# Output_Display.net
KiCad netlist of a schematic drawn in Altium Designer
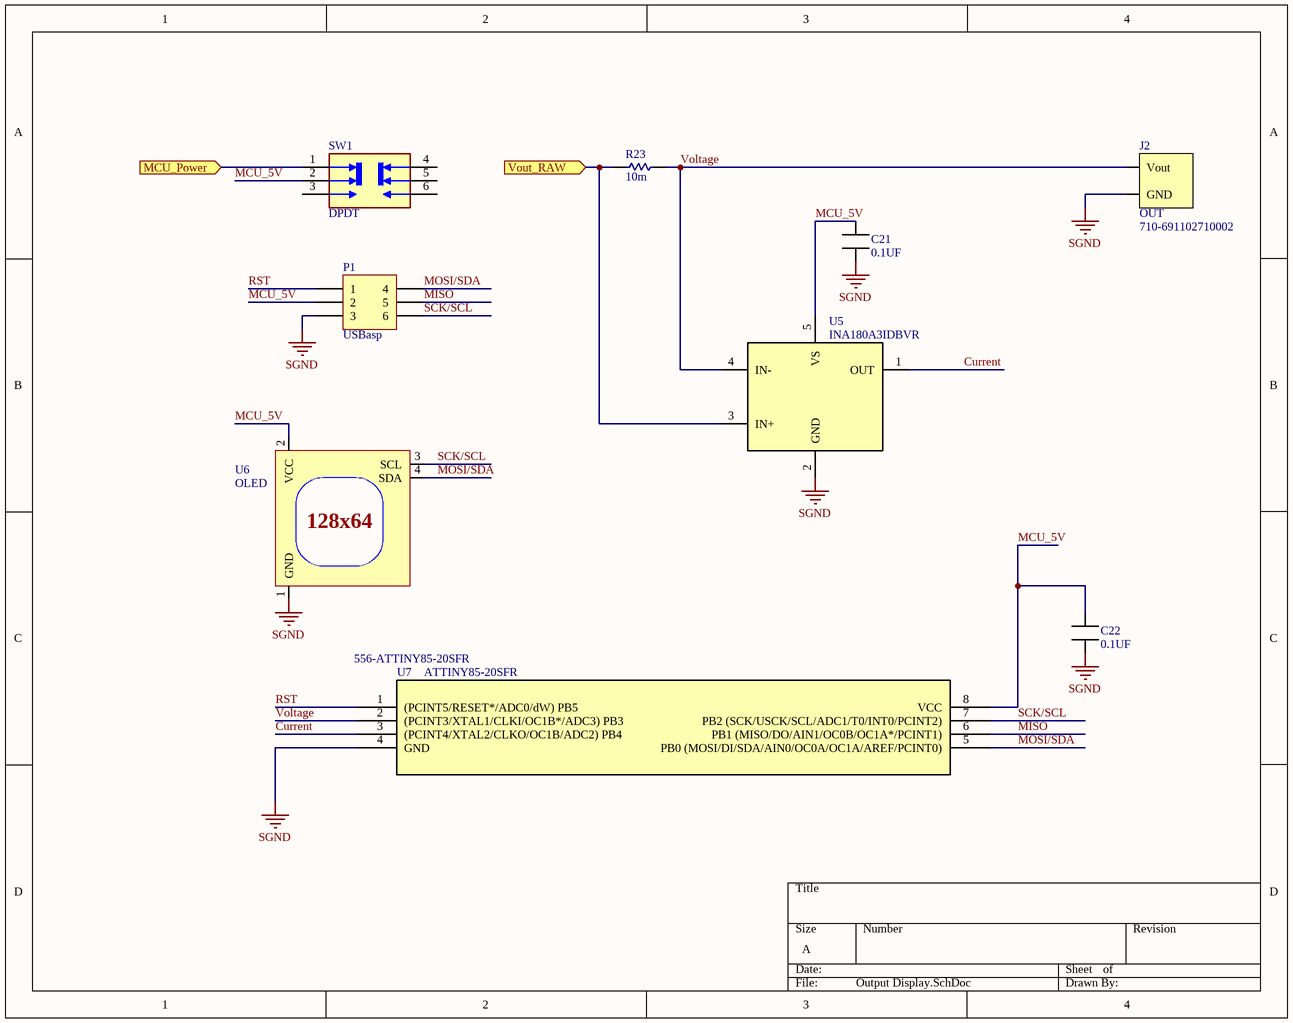
[diagram p0: Output Display.SchDoc]

(export (version "E")
  (design (tool "Eeschema 10.0.6"))
  (components
    (comp (ref "C21")
      (value "0.1UF")
      (footprint "Cap 0603")
      (description "Multilayer Ceramic Capacitors MLCC - SMD/SMT 25V 0.1uF X7R 0603 10%")
      (libsource (lib "SMPS Schlib") (part "C0603C104K3RAC"))
    )
    (comp (ref "C22")
      (value "0.1UF")
      (footprint "Cap 0603")
      (description "Multilayer Ceramic Capacitors MLCC - SMD/SMT 25V 0.1uF X7R 0603 10%")
      (libsource (lib "SMPS Schlib") (part "C0603C104K3RAC"))
    )
    (comp (ref "J2")
      (value "OUT")
      (footprint "691102710002")
      (description "Fixed Terminal Blocks WR-TBL 300VAC 15A 2P Straight")
      (fields (field (name "SUPPLIER PART NUMBER 1") "710-691102710002"))
      (libsource (lib "SMPS Schlib") (part "691102710002"))
    )
    (comp (ref "P1")
      (value "USBasp")
      (footprint "HDR2X3_CEN")
      (description "Header, 3-Pin, Dual row")
      (fields (field (name "PUBLISHER") "Altium Limited"))
      (libsource (lib "Miscellaneous Connectors") (part "Header 3X2A"))
    )
    (comp (ref "R23")
      (value "10m")
      (footprint "Cap 1206")
      (description "Current Sense Resistors - SMD 10mOhms 1/4W 50PPM/C 1 % 1206 AEC-Q200")
      (libsource (lib "SMPS Schlib") (part "PA1206FRE070R01Z"))
    )
    (comp (ref "SW1")
      (value "DPDT")
      (footprint "JS2020")
      (description "SWITCH SLIDE DPDT 300MA 6V")
      (libsource (lib "SMPS Schlib") (part "JS202011SCQN"))
    )
    (comp (ref "U5")
      (value "INA180A3IDBVR")
      (footprint "SOT-23-5")
      (description "Current Sense Amplifiers 26V, 350kHz current sense amplifier 5-SOT-23 -40 to 125")
      (libsource (lib "SMPS Schlib") (part "INA180A3IDBVR"))
    )
    (comp (ref "U6")
      (value "OLED")
      (footprint "OLED")
      (description "0.96″ OLED 4pin LCD LED Display Module I2C IIC Communicate – White 128×64")
      (libsource (lib "SMPS Schlib") (part "0.96 inch OLED"))
    )
    (comp (ref "U7")
      (value "ATTINY85-20SFR")
      (footprint "SOIC 8 ATTINY")
      (description "8-bit Microcontrollers - MCU AVR 8K FLSH 512B EE 512B SRAM ADC 5V")
      (fields (field (name "SUPPLIER PART NUMBER 1") "556-ATTINY85-20SFR"))
      (libsource (lib "SMPS Schlib") (part "ATTINY85-20SU"))
    )
  )
  (nets
    (net (code "1") (name "/Current") (class "Default")
      (node (ref "U5") (pin "1") (pinfunction "OUT_1") (pintype "passive"))
      (node (ref "U7") (pin "3") (pinfunction "(PCINT4/XTAL2/CLKO/OC1B/ADC2)_PB4_3") (pintype "passive"))
    )
    (net (code "2") (name "/MCU_5V") (class "Default")
      (node (ref "C21") (pin "2") (pinfunction "2_2") (pintype "passive"))
      (node (ref "C22") (pin "2") (pinfunction "2_2") (pintype "passive"))
      (node (ref "P1") (pin "2") (pinfunction "2_2") (pintype "passive"))
      (node (ref "SW1") (pin "2") (pinfunction "2_2") (pintype "passive"))
      (node (ref "U5") (pin "5") (pinfunction "VS_5") (pintype "power_in"))
      (node (ref "U6") (pin "2") (pinfunction "VCC_2") (pintype "passive"))
      (node (ref "U7") (pin "8") (pinfunction "VCC_8") (pintype "passive"))
    )
    (net (code "3") (name "/MCU_Power") (class "Default")
      (node (ref "SW1") (pin "1") (pinfunction "1_1") (pintype "passive"))
    )
    (net (code "4") (name "/MISO") (class "Default")
      (node (ref "P1") (pin "5") (pinfunction "5_5") (pintype "passive"))
      (node (ref "U7") (pin "6") (pinfunction "PB1_(MISO/DO/AIN1/OC0B/OC1A*/PCINT1)_6") (pintype "passive"))
    )
    (net (code "5") (name "/MOSI{slash}SDA") (class "Default")
      (node (ref "P1") (pin "4") (pinfunction "4_4") (pintype "passive"))
      (node (ref "U6") (pin "4") (pinfunction "SDA_4") (pintype "passive"))
      (node (ref "U7") (pin "5") (pinfunction "PB0_(MOSI/DI/SDA/AIN0/OC0A/OC1A/AREF/PCINT0)_5") (pintype "passive"))
    )
    (net (code "6") (name "/RST") (class "Default")
      (node (ref "P1") (pin "1") (pinfunction "1_1") (pintype "passive"))
      (node (ref "U7") (pin "1") (pinfunction "(PCINT5/RESET*/ADC0/dW)_PB5_1") (pintype "passive"))
    )
    (net (code "7") (name "/SCK{slash}SCL") (class "Default")
      (node (ref "P1") (pin "6") (pinfunction "6_6") (pintype "passive"))
      (node (ref "U6") (pin "3") (pinfunction "SCL_3") (pintype "passive"))
      (node (ref "U7") (pin "7") (pinfunction "PB2_(SCK/USCK/SCL/ADC1/T0/INT0/PCINT2)_7") (pintype "passive"))
    )
    (net (code "8") (name "/Voltage") (class "Default")
      (node (ref "J2") (pin "1") (pinfunction "Vout_1") (pintype "passive"))
      (node (ref "R23") (pin "2") (pinfunction "B_2") (pintype "passive"))
      (node (ref "U5") (pin "4") (pinfunction "IN-_4") (pintype "passive"))
      (node (ref "U7") (pin "2") (pinfunction "(PCINT3/XTAL1/CLKI/OC1B*/ADC3)_PB3_2") (pintype "passive"))
    )
    (net (code "9") (name "/Vout_RAW") (class "Default")
      (node (ref "R23") (pin "1") (pinfunction "A_1") (pintype "passive"))
      (node (ref "U5") (pin "3") (pinfunction "IN+_3") (pintype "passive"))
    )
    (net (code "10") (name "SGND") (class "Default")
      (node (ref "C21") (pin "1") (pinfunction "1_1") (pintype "passive"))
      (node (ref "C22") (pin "1") (pinfunction "1_1") (pintype "passive"))
      (node (ref "J2") (pin "2") (pinfunction "GND_2") (pintype "passive"))
      (node (ref "P1") (pin "3") (pinfunction "3_3") (pintype "passive"))
      (node (ref "U5") (pin "2") (pinfunction "GND_2") (pintype "power_in"))
      (node (ref "U6") (pin "1") (pinfunction "GND_1") (pintype "passive"))
      (node (ref "U7") (pin "4") (pinfunction "GND_4") (pintype "passive"))
    )
    (net (code "11") (name "unconnected-(SW1-Pad3)") (class "Default")
      (node (ref "SW1") (pin "3") (pinfunction "3_3") (pintype "passive"))
    )
    (net (code "12") (name "unconnected-(SW1-Pad4)") (class "Default")
      (node (ref "SW1") (pin "4") (pinfunction "4_4") (pintype "passive"))
    )
    (net (code "13") (name "unconnected-(SW1-Pad5)") (class "Default")
      (node (ref "SW1") (pin "5") (pinfunction "5_5") (pintype "passive"))
    )
    (net (code "14") (name "unconnected-(SW1-Pad6)") (class "Default")
      (node (ref "SW1") (pin "6") (pinfunction "6_6") (pintype "passive"))
    )
  )
)
